# FastTrig_Board.net
KiCad netlist of a schematic drawn in Altium Designer
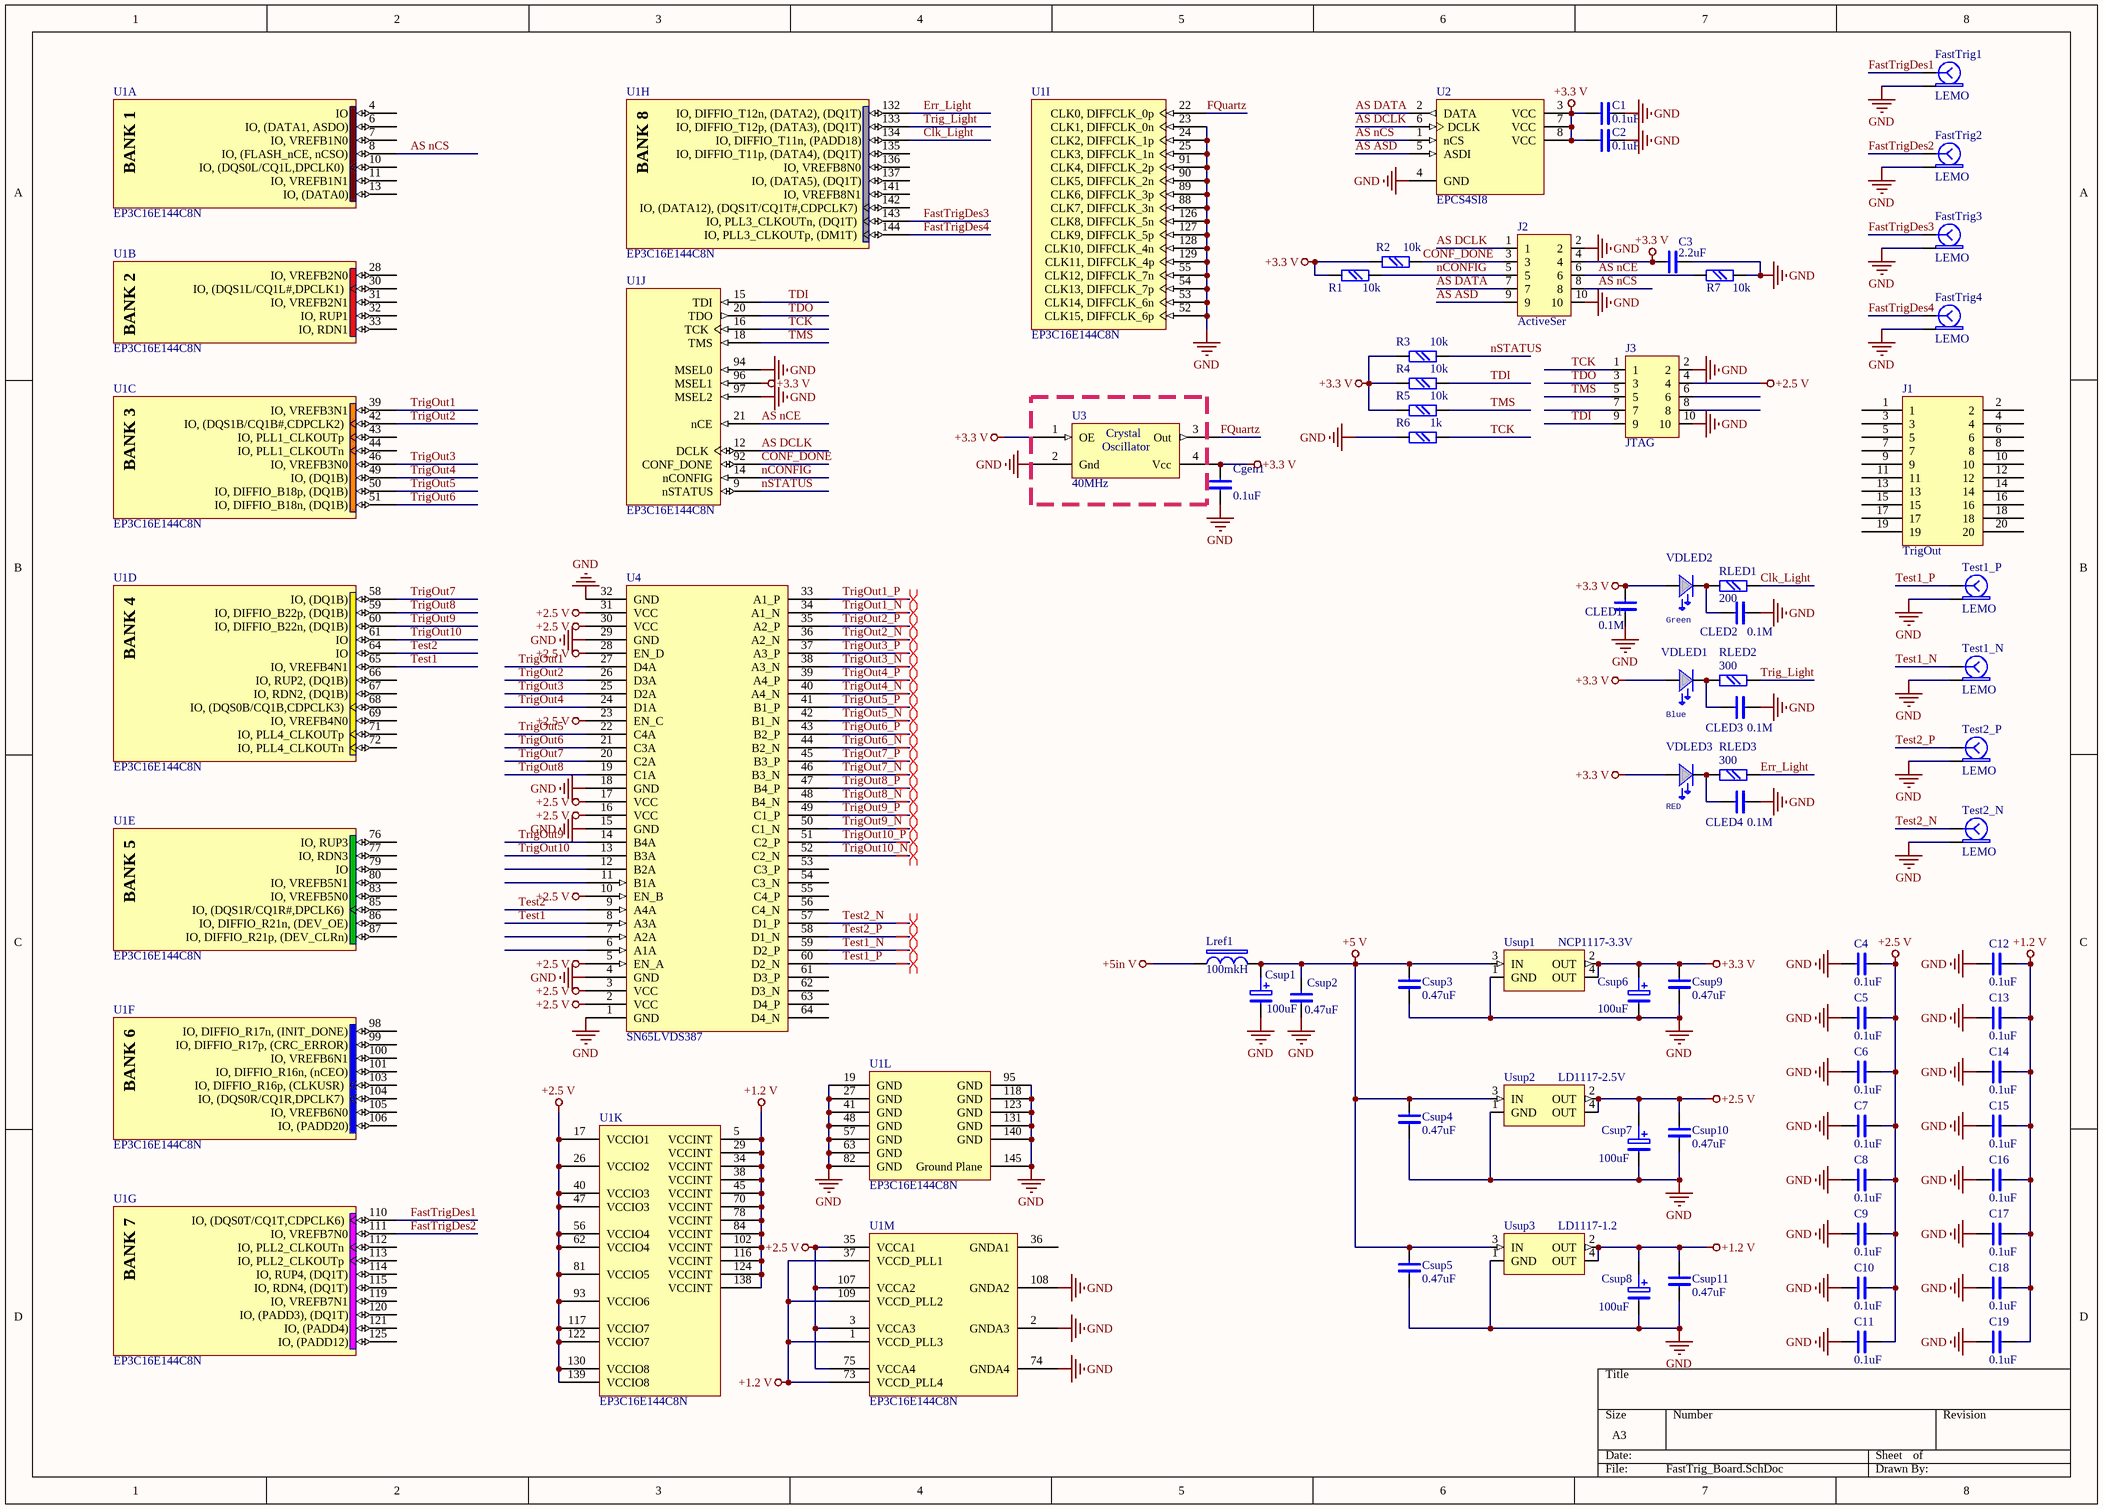
[diagram p0: FastTrig_Board.SchDoc]

(export (version "E")
  (design (tool "Eeschema 10.0.6"))
  (components
    (comp (ref "C1") (value "0.1uF") (footprint "chip0603") (libsource (lib "") (part "C_1")))
    (comp (ref "C2") (value "0.1uF") (footprint "chip0603") (libsource (lib "") (part "C_1")))
    (comp (ref "C3") (value "2.2uF") (footprint "chip0603") (libsource (lib "") (part "C_1")))
    (comp (ref "C4") (value "0.1uF") (footprint "chip0402") (libsource (lib "") (part "C_1")))
    (comp (ref "C5") (value "0.1uF") (footprint "chip0402") (libsource (lib "") (part "C_1")))
    (comp (ref "C6") (value "0.1uF") (footprint "chip0402") (libsource (lib "") (part "C_1")))
    (comp (ref "C7") (value "0.1uF") (footprint "chip0402") (libsource (lib "") (part "C_1")))
    (comp (ref "C8") (value "0.1uF") (footprint "chip0402") (libsource (lib "") (part "C_1")))
    (comp (ref "C9") (value "0.1uF") (footprint "chip0402") (libsource (lib "") (part "C_1")))
    (comp (ref "C10") (value "0.1uF") (footprint "chip0402") (libsource (lib "") (part "C_1")))
    (comp (ref "C11") (value "0.1uF") (footprint "chip0402") (libsource (lib "") (part "C_1")))
    (comp (ref "C12") (value "0.1uF") (footprint "chip0402") (libsource (lib "") (part "C_1")))
    (comp (ref "C13") (value "0.1uF") (footprint "chip0402") (libsource (lib "") (part "C_1")))
    (comp (ref "C14") (value "0.1uF") (footprint "chip0402") (libsource (lib "") (part "C_1")))
    (comp (ref "C15") (value "0.1uF") (footprint "chip0402") (libsource (lib "") (part "C_1")))
    (comp (ref "C16") (value "0.1uF") (footprint "chip0402") (libsource (lib "") (part "C_1")))
    (comp (ref "C17") (value "0.1uF") (footprint "chip0402") (libsource (lib "") (part "C_1")))
    (comp (ref "C18") (value "0.1uF") (footprint "chip0402") (libsource (lib "") (part "C_1")))
    (comp (ref "C19") (value "0.1uF") (footprint "chip0402") (libsource (lib "") (part "C_1")))
    (comp (ref "Cgen1") (value "0.1uF") (footprint "chip0603") (libsource (lib "*") (part "C")))
    (comp (ref "CLED1") (value "0.1M") (footprint "chip0805") (libsource (lib "") (part "C_1")))
    (comp (ref "CLED2") (value "0.1M") (footprint "chip0805") (libsource (lib "") (part "C_1")))
    (comp (ref "CLED3") (value "0.1M") (footprint "chip0805") (libsource (lib "") (part "C_1")))
    (comp (ref "CLED4") (value "0.1M") (footprint "chip0805") (libsource (lib "") (part "C_1")))
    (comp (ref "Csup1") (value "100uF") (footprint "CEL-SMD300") (libsource (lib "*") (part "C POL")))
    (comp (ref "Csup2") (value "0.47uF") (footprint "chip0603") (libsource (lib "*") (part "C")))
    (comp (ref "Csup3") (value "0.47uF") (footprint "chip0603") (libsource (lib "*") (part "C")))
    (comp (ref "Csup4") (value "0.47uF") (footprint "chip0603") (libsource (lib "*") (part "C")))
    (comp (ref "Csup5") (value "0.47uF") (footprint "chip0603") (libsource (lib "*") (part "C")))
    (comp (ref "Csup6") (value "100uF") (footprint "CEL-SMD300") (libsource (lib "*") (part "C POL")))
    (comp (ref "Csup7") (value "100uF") (footprint "CEL-SMD300") (libsource (lib "*") (part "C POL")))
    (comp (ref "Csup8") (value "100uF") (footprint "CEL-SMD300") (libsource (lib "*") (part "C POL")))
    (comp (ref "Csup9") (value "0.47uF") (footprint "chip0603") (libsource (lib "*") (part "C")))
    (comp (ref "Csup10") (value "0.47uF") (footprint "chip0603") (libsource (lib "*") (part "C")))
    (comp (ref "Csup11") (value "0.47uF") (footprint "chip0603") (libsource (lib "*") (part "C")))
    (comp (ref "FastTrig1") (value "LEMO") (footprint "LEMO") (libsource (lib "vDevice") (part "LEMO")))
    (comp (ref "FastTrig2") (value "LEMO") (footprint "LEMO") (libsource (lib "vDevice") (part "LEMO")))
    (comp (ref "FastTrig3") (value "LEMO") (footprint "LEMO") (libsource (lib "vDevice") (part "LEMO")))
    (comp (ref "FastTrig4") (value "LEMO") (footprint "LEMO") (libsource (lib "vDevice") (part "LEMO")))
    (comp (ref "J1")
      (value "TrigOut")
      (footprint "IDC-20_2x10_1.27")
      (libsource (lib "vDevice") (part "IDC-20_2x10_1.27"))
    )
    (comp (ref "J2") (value "ActiveSer") (footprint "IDC10") (libsource (lib "vDevice") (part "IDC-10")))
    (comp (ref "J3") (value "JTAG") (footprint "IDC10") (libsource (lib "vDevice") (part "IDC-10")))
    (comp (ref "Lref1") (value "100mkH") (footprint "SDR0604") (libsource (lib "*") (part "DR")))
    (comp (ref "R1") (value "10k") (footprint "chip0603") (libsource (lib "*") (part "R")))
    (comp (ref "R2") (value "10k") (footprint "chip0603") (libsource (lib "*") (part "R")))
    (comp (ref "R3") (value "10k") (footprint "chip0603") (libsource (lib "*") (part "R")))
    (comp (ref "R4") (value "10k") (footprint "chip0603") (libsource (lib "*") (part "R")))
    (comp (ref "R5") (value "10k") (footprint "chip0603") (libsource (lib "*") (part "R")))
    (comp (ref "R6") (value "1k") (footprint "chip0603") (libsource (lib "*") (part "R")))
    (comp (ref "R7") (value "10k") (footprint "chip0603") (libsource (lib "*") (part "R")))
    (comp (ref "RLED1") (value "200") (footprint "chip0805") (libsource (lib "*") (part "R")))
    (comp (ref "RLED2") (value "300") (footprint "chip0805") (libsource (lib "*") (part "R")))
    (comp (ref "RLED3") (value "300") (footprint "chip0805") (libsource (lib "*") (part "R")))
    (comp (ref "Test1_N") (value "LEMO") (footprint "LEMO") (libsource (lib "vDevice") (part "LEMO")))
    (comp (ref "Test1_P") (value "LEMO") (footprint "LEMO") (libsource (lib "vDevice") (part "LEMO")))
    (comp (ref "Test2_N") (value "LEMO") (footprint "LEMO") (libsource (lib "vDevice") (part "LEMO")))
    (comp (ref "Test2_P") (value "LEMO") (footprint "LEMO") (libsource (lib "vDevice") (part "LEMO")))
    (comp (ref "U1")
      (value "EP3C16E144C8N")
      (footprint "EQFP144_N")
      (fields (field (name "PUBLISHER") "Altium Limited"))
      (libsource (lib "") (part "EP3C16E144C8N_1"))
    )
    (comp (ref "U2")
      (value "EPCS4SI8")
      (footprint "8SO200")
      (fields (field (name "PUBLISHER") "Altium Limited"))
      (libsource (lib "Altera EPCS Configuration Device") (part "EPCS4SI8"))
    )
    (comp (ref "U3")
      (value "40MHz")
      (footprint "SG-636")
      (description "Crystal Oscillator (SMD)")
      (libsource (lib "*") (part "SG-636"))
    )
    (comp (ref "U4")
      (value "SN65LVDS387")
      (footprint "DGG064")
      (libsource (lib "vDigital") (part "SN65LVDS387"))
    )
    (comp (ref "Usup1")
      (value "NCP1117-3.3V")
      (footprint "TO-252")
      (libsource (lib "vAnalog") (part "NCP1117-3.3V"))
    )
    (comp (ref "Usup2")
      (value "LD1117-2.5V")
      (footprint "TO-252")
      (libsource (lib "vAnalog") (part "NCP1117-3.3V"))
    )
    (comp (ref "Usup3")
      (value "LD1117-1.2")
      (footprint "TO-252")
      (libsource (lib "vAnalog") (part "NCP1117-3.3V"))
    )
    (comp (ref "VDLED1") (value "LED") (footprint "CHIP1206") (libsource (lib "*") (part "AL307")))
    (comp (ref "VDLED2") (value "LED") (footprint "CHIP0805") (libsource (lib "*") (part "AL307")))
    (comp (ref "VDLED3") (value "LED") (footprint "CHIP1206") (libsource (lib "*") (part "AL307")))
  )
  (nets
    (net (code "1") (name "+1.2 V") (class "Default")
      (node (ref "C12") (pin "2") (pinfunction "2_2") (pintype "passive"))
      (node (ref "C13") (pin "2") (pinfunction "2_2") (pintype "passive"))
      (node (ref "C14") (pin "2") (pinfunction "2_2") (pintype "passive"))
      (node (ref "C15") (pin "2") (pinfunction "2_2") (pintype "passive"))
      (node (ref "C16") (pin "2") (pinfunction "2_2") (pintype "passive"))
      (node (ref "C17") (pin "2") (pinfunction "2_2") (pintype "passive"))
      (node (ref "C18") (pin "2") (pinfunction "2_2") (pintype "passive"))
      (node (ref "C19") (pin "2") (pinfunction "2_2") (pintype "passive"))
      (node (ref "Csup11") (pin "1") (pinfunction "1_1") (pintype "passive"))
      (node (ref "Csup8") (pin "+") (pinfunction "+_+") (pintype "passive"))
      (node (ref "U1") (pin "1") (pinfunction "VCCD_PLL3_1") (pintype "power_in"))
      (node (ref "U1") (pin "102") (pinfunction "VCCINT_102") (pintype "power_in"))
      (node (ref "U1") (pin "109") (pinfunction "VCCD_PLL2_109") (pintype "power_in"))
      (node (ref "U1") (pin "116") (pinfunction "VCCINT_116") (pintype "power_in"))
      (node (ref "U1") (pin "124") (pinfunction "VCCINT_124") (pintype "power_in"))
      (node (ref "U1") (pin "138") (pinfunction "VCCINT_138") (pintype "power_in"))
      (node (ref "U1") (pin "29") (pinfunction "VCCINT_29") (pintype "power_in"))
      (node (ref "U1") (pin "34") (pinfunction "VCCINT_34") (pintype "power_in"))
      (node (ref "U1") (pin "37") (pinfunction "VCCD_PLL1_37") (pintype "power_in"))
      (node (ref "U1") (pin "38") (pinfunction "VCCINT_38") (pintype "power_in"))
      (node (ref "U1") (pin "45") (pinfunction "VCCINT_45") (pintype "power_in"))
      (node (ref "U1") (pin "5") (pinfunction "VCCINT_5") (pintype "power_in"))
      (node (ref "U1") (pin "70") (pinfunction "VCCINT_70") (pintype "power_in"))
      (node (ref "U1") (pin "73") (pinfunction "VCCD_PLL4_73") (pintype "power_in"))
      (node (ref "U1") (pin "78") (pinfunction "VCCINT_78") (pintype "power_in"))
      (node (ref "U1") (pin "84") (pinfunction "VCCINT_84") (pintype "power_in"))
      (node (ref "Usup3") (pin "2") (pinfunction "OUT_2") (pintype "output"))
      (node (ref "Usup3") (pin "4") (pinfunction "OUT_4") (pintype "passive"))
    )
    (net (code "2") (name "+2.5 V") (class "Default")
      (node (ref "C10") (pin "2") (pinfunction "2_2") (pintype "passive"))
      (node (ref "C11") (pin "2") (pinfunction "2_2") (pintype "passive"))
      (node (ref "C4") (pin "2") (pinfunction "2_2") (pintype "passive"))
      (node (ref "C5") (pin "2") (pinfunction "2_2") (pintype "passive"))
      (node (ref "C6") (pin "2") (pinfunction "2_2") (pintype "passive"))
      (node (ref "C7") (pin "2") (pinfunction "2_2") (pintype "passive"))
      (node (ref "C8") (pin "2") (pinfunction "2_2") (pintype "passive"))
      (node (ref "C9") (pin "2") (pinfunction "2_2") (pintype "passive"))
      (node (ref "Csup10") (pin "1") (pinfunction "1_1") (pintype "passive"))
      (node (ref "Csup7") (pin "+") (pinfunction "+_+") (pintype "passive"))
      (node (ref "J3") (pin "4") (pinfunction "4_4") (pintype "bidirectional"))
      (node (ref "U1") (pin "107") (pinfunction "VCCA2_107") (pintype "power_in"))
      (node (ref "U1") (pin "117") (pinfunction "VCCIO7_117") (pintype "power_in"))
      (node (ref "U1") (pin "122") (pinfunction "VCCIO7_122") (pintype "power_in"))
      (node (ref "U1") (pin "130") (pinfunction "VCCIO8_130") (pintype "power_in"))
      (node (ref "U1") (pin "139") (pinfunction "VCCIO8_139") (pintype "power_in"))
      (node (ref "U1") (pin "17") (pinfunction "VCCIO1_17") (pintype "power_in"))
      (node (ref "U1") (pin "26") (pinfunction "VCCIO2_26") (pintype "power_in"))
      (node (ref "U1") (pin "3") (pinfunction "VCCA3_3") (pintype "power_in"))
      (node (ref "U1") (pin "35") (pinfunction "VCCA1_35") (pintype "power_in"))
      (node (ref "U1") (pin "40") (pinfunction "VCCIO3_40") (pintype "power_in"))
      (node (ref "U1") (pin "47") (pinfunction "VCCIO3_47") (pintype "power_in"))
      (node (ref "U1") (pin "56") (pinfunction "VCCIO4_56") (pintype "power_in"))
      (node (ref "U1") (pin "62") (pinfunction "VCCIO4_62") (pintype "power_in"))
      (node (ref "U1") (pin "75") (pinfunction "VCCA4_75") (pintype "power_in"))
      (node (ref "U1") (pin "81") (pinfunction "VCCIO5_81") (pintype "power_in"))
      (node (ref "U1") (pin "93") (pinfunction "VCCIO6_93") (pintype "power_in"))
      (node (ref "U4") (pin "10") (pinfunction "EN_B_10") (pintype "input"))
      (node (ref "U4") (pin "16") (pinfunction "VCC_16") (pintype "power_in"))
      (node (ref "U4") (pin "17") (pinfunction "VCC_17") (pintype "power_in"))
      (node (ref "U4") (pin "2") (pinfunction "VCC_2") (pintype "power_in"))
      (node (ref "U4") (pin "23") (pinfunction "EN_C_23") (pintype "passive"))
      (node (ref "U4") (pin "28") (pinfunction "EN_D_28") (pintype "passive"))
      (node (ref "U4") (pin "3") (pinfunction "VCC_3") (pintype "power_in"))
      (node (ref "U4") (pin "30") (pinfunction "VCC_30") (pintype "power_in"))
      (node (ref "U4") (pin "31") (pinfunction "VCC_31") (pintype "power_in"))
      (node (ref "U4") (pin "5") (pinfunction "EN_A_5") (pintype "input"))
      (node (ref "Usup2") (pin "2") (pinfunction "OUT_2") (pintype "output"))
      (node (ref "Usup2") (pin "4") (pinfunction "OUT_4") (pintype "passive"))
    )
    (net (code "3") (name "+3.3 V") (class "Default")
      (node (ref "C1") (pin "2") (pinfunction "2_2") (pintype "passive"))
      (node (ref "C2") (pin "2") (pinfunction "2_2") (pintype "passive"))
      (node (ref "C3") (pin "1") (pinfunction "1_1") (pintype "passive"))
      (node (ref "CLED1") (pin "1") (pinfunction "1_1") (pintype "passive"))
      (node (ref "Cgen1") (pin "2") (pinfunction "2_2") (pintype "passive"))
      (node (ref "Csup6") (pin "+") (pinfunction "+_+") (pintype "passive"))
      (node (ref "Csup9") (pin "1") (pinfunction "1_1") (pintype "passive"))
      (node (ref "J2") (pin "4") (pinfunction "4_4") (pintype "bidirectional"))
      (node (ref "R1") (pin "1") (pinfunction "1_1") (pintype "passive"))
      (node (ref "R2") (pin "1") (pinfunction "1_1") (pintype "passive"))
      (node (ref "R3") (pin "1") (pinfunction "1_1") (pintype "passive"))
      (node (ref "R4") (pin "1") (pinfunction "1_1") (pintype "passive"))
      (node (ref "R5") (pin "1") (pinfunction "1_1") (pintype "passive"))
      (node (ref "U1") (pin "96") (pinfunction "MSEL1_96") (pintype "input"))
      (node (ref "U2") (pin "3") (pinfunction "VCC_3") (pintype "power_in"))
      (node (ref "U2") (pin "7") (pinfunction "VCC_7") (pintype "power_in"))
      (node (ref "U2") (pin "8") (pinfunction "VCC_8") (pintype "power_in"))
      (node (ref "U3") (pin "1") (pinfunction "OE_1") (pintype "input"))
      (node (ref "U3") (pin "4") (pinfunction "Vcc_4") (pintype "power_in"))
      (node (ref "Usup1") (pin "2") (pinfunction "OUT_2") (pintype "output"))
      (node (ref "Usup1") (pin "4") (pinfunction "OUT_4") (pintype "passive"))
      (node (ref "VDLED1") (pin "ANOD") (pinfunction "ANOD_ANOD") (pintype "passive"))
      (node (ref "VDLED2") (pin "ANOD") (pinfunction "ANOD_ANOD") (pintype "passive"))
      (node (ref "VDLED3") (pin "ANOD") (pinfunction "ANOD_ANOD") (pintype "passive"))
    )
    (net (code "4") (name "+5 V") (class "Default")
      (node (ref "Csup1") (pin "+") (pinfunction "+_+") (pintype "passive"))
      (node (ref "Csup2") (pin "1") (pinfunction "1_1") (pintype "passive"))
      (node (ref "Csup3") (pin "1") (pinfunction "1_1") (pintype "passive"))
      (node (ref "Csup4") (pin "1") (pinfunction "1_1") (pintype "passive"))
      (node (ref "Csup5") (pin "1") (pinfunction "1_1") (pintype "passive"))
      (node (ref "Lref1") (pin "2") (pinfunction "2_2") (pintype "passive"))
      (node (ref "Usup1") (pin "3") (pinfunction "IN_3") (pintype "input"))
      (node (ref "Usup2") (pin "3") (pinfunction "IN_3") (pintype "input"))
      (node (ref "Usup3") (pin "3") (pinfunction "IN_3") (pintype "input"))
    )
    (net (code "5") (name "+5in V") (class "Default")
      (node (ref "Lref1") (pin "1") (pinfunction "1_1") (pintype "passive"))
    )
    (net (code "6") (name "/AS ASD") (class "Default")
      (node (ref "J2") (pin "9") (pinfunction "9_9") (pintype "bidirectional"))
      (node (ref "U2") (pin "5") (pinfunction "ASDI_5") (pintype "input"))
    )
    (net (code "7") (name "/AS DATA") (class "Default")
      (node (ref "J2") (pin "7") (pinfunction "7_7") (pintype "bidirectional"))
      (node (ref "U2") (pin "2") (pinfunction "DATA_2") (pintype "output"))
    )
    (net (code "8") (name "/AS DCLK") (class "Default")
      (node (ref "J2") (pin "1") (pinfunction "1_1") (pintype "bidirectional"))
      (node (ref "U1") (pin "12") (pinfunction "DCLK_12") (pintype "bidirectional"))
      (node (ref "U2") (pin "6") (pinfunction "DCLK_6") (pintype "input"))
    )
    (net (code "9") (name "/AS nCE") (class "Default")
      (node (ref "J2") (pin "6") (pinfunction "6_6") (pintype "bidirectional"))
      (node (ref "R7") (pin "1") (pinfunction "1_1") (pintype "passive"))
      (node (ref "U1") (pin "21") (pinfunction "nCE_21") (pintype "input"))
    )
    (net (code "10") (name "/AS nCS") (class "Default")
      (node (ref "J2") (pin "8") (pinfunction "8_8") (pintype "bidirectional"))
      (node (ref "U1") (pin "8") (pinfunction "IO,_(FLASH_nCE,_nCSO)_8") (pintype "bidirectional"))
      (node (ref "U2") (pin "1") (pinfunction "nCS_1") (pintype "input"))
    )
    (net (code "11") (name "/CONF_DONE") (class "Default")
      (node (ref "J2") (pin "3") (pinfunction "3_3") (pintype "bidirectional"))
      (node (ref "R2") (pin "2") (pinfunction "2_2") (pintype "passive"))
      (node (ref "U1") (pin "92") (pinfunction "CONF_DONE_92") (pintype "bidirectional"))
    )
    (net (code "12") (name "/Clk_Light") (class "Default")
      (node (ref "RLED1") (pin "2") (pinfunction "2_2") (pintype "passive"))
      (node (ref "U1") (pin "134") (pinfunction "IO,_DIFFIO_T11n,_(PADD18)_134") (pintype "bidirectional"))
    )
    (net (code "13") (name "/Err_Light") (class "Default")
      (node (ref "RLED3") (pin "2") (pinfunction "2_2") (pintype "passive"))
      (node (ref "U1") (pin "132") (pinfunction "IO,_DIFFIO_T12n,_(DATA2),_(DQ1T)_132") (pintype "bidirectional"))
    )
    (net (code "14") (name "/FQuartz") (class "Default")
      (node (ref "U1") (pin "22") (pinfunction "CLK0,_DIFFCLK_0p_22") (pintype "input"))
      (node (ref "U3") (pin "3") (pinfunction "Out_3") (pintype "output"))
    )
    (net (code "15") (name "/FastTrigDes1") (class "Default")
      (node (ref "FastTrig1") (pin "WIRE") (pinfunction "WIRE_WIRE") (pintype "bidirectional"))
      (node (ref "U1") (pin "110") (pinfunction "IO,_(DQS0T/CQ1T,CDPCLK6)_110") (pintype "bidirectional"))
    )
    (net (code "16") (name "/FastTrigDes2") (class "Default")
      (node (ref "FastTrig2") (pin "WIRE") (pinfunction "WIRE_WIRE") (pintype "bidirectional"))
      (node (ref "U1") (pin "111") (pinfunction "IO,_VREFB7N0_111") (pintype "bidirectional"))
    )
    (net (code "17") (name "/FastTrigDes3") (class "Default")
      (node (ref "FastTrig3") (pin "WIRE") (pinfunction "WIRE_WIRE") (pintype "bidirectional"))
      (node (ref "U1") (pin "143") (pinfunction "IO,_PLL3_CLKOUTn,_(DQ1T)_143") (pintype "bidirectional"))
    )
    (net (code "18") (name "/FastTrigDes4") (class "Default")
      (node (ref "FastTrig4") (pin "WIRE") (pinfunction "WIRE_WIRE") (pintype "bidirectional"))
      (node (ref "U1") (pin "144") (pinfunction "IO,_PLL3_CLKOUTp,_(DM1T)_144") (pintype "bidirectional"))
    )
    (net (code "19") (name "/TCK") (class "Default")
      (node (ref "J3") (pin "1") (pinfunction "1_1") (pintype "bidirectional"))
      (node (ref "R6") (pin "2") (pinfunction "2_2") (pintype "passive"))
      (node (ref "U1") (pin "16") (pinfunction "TCK_16") (pintype "input"))
    )
    (net (code "20") (name "/TDI") (class "Default")
      (node (ref "J3") (pin "9") (pinfunction "9_9") (pintype "bidirectional"))
      (node (ref "R4") (pin "2") (pinfunction "2_2") (pintype "passive"))
      (node (ref "U1") (pin "15") (pinfunction "TDI_15") (pintype "input"))
    )
    (net (code "21") (name "/TDO") (class "Default")
      (node (ref "J3") (pin "3") (pinfunction "3_3") (pintype "bidirectional"))
      (node (ref "U1") (pin "20") (pinfunction "TDO_20") (pintype "output"))
    )
    (net (code "22") (name "/TMS") (class "Default")
      (node (ref "J3") (pin "5") (pinfunction "5_5") (pintype "bidirectional"))
      (node (ref "R5") (pin "2") (pinfunction "2_2") (pintype "passive"))
      (node (ref "U1") (pin "18") (pinfunction "TMS_18") (pintype "input"))
    )
    (net (code "23") (name "/Test1") (class "Default")
      (node (ref "U1") (pin "65") (pinfunction "IO,_VREFB4N1_65") (pintype "bidirectional"))
      (node (ref "U4") (pin "8") (pinfunction "A3A_8") (pintype "input"))
    )
    (net (code "24") (name "/Test1_N") (class "Default")
      (node (ref "Test1_N") (pin "WIRE") (pinfunction "WIRE_WIRE") (pintype "bidirectional"))
      (node (ref "U4") (pin "59") (pinfunction "D2_P_59") (pintype "passive"))
    )
    (net (code "25") (name "/Test1_P") (class "Default")
      (node (ref "Test1_P") (pin "WIRE") (pinfunction "WIRE_WIRE") (pintype "bidirectional"))
      (node (ref "U4") (pin "60") (pinfunction "D2_N_60") (pintype "passive"))
    )
    (net (code "26") (name "/Test2") (class "Default")
      (node (ref "U1") (pin "64") (pinfunction "IO_64") (pintype "bidirectional"))
      (node (ref "U4") (pin "9") (pinfunction "A4A_9") (pintype "input"))
    )
    (net (code "27") (name "/Test2_N") (class "Default")
      (node (ref "Test2_N") (pin "WIRE") (pinfunction "WIRE_WIRE") (pintype "bidirectional"))
      (node (ref "U4") (pin "57") (pinfunction "D1_P_57") (pintype "passive"))
    )
    (net (code "28") (name "/Test2_P") (class "Default")
      (node (ref "Test2_P") (pin "WIRE") (pinfunction "WIRE_WIRE") (pintype "bidirectional"))
      (node (ref "U4") (pin "58") (pinfunction "D1_N_58") (pintype "passive"))
    )
    (net (code "29") (name "/TrigOut1") (class "Default")
      (node (ref "U1") (pin "39") (pinfunction "IO,_VREFB3N1_39") (pintype "bidirectional"))
      (node (ref "U4") (pin "27") (pinfunction "D4A_27") (pintype "passive"))
    )
    (net (code "30") (name "/TrigOut1_N") (class "Default")
      (node (ref "U4") (pin "34") (pinfunction "A1_N_34") (pintype "passive"))
    )
    (net (code "31") (name "/TrigOut1_P") (class "Default")
      (node (ref "U4") (pin "33") (pinfunction "A1_P_33") (pintype "passive"))
    )
    (net (code "32") (name "/TrigOut2") (class "Default")
      (node (ref "U1") (pin "42") (pinfunction "IO,_(DQS1B/CQ1B#,CDPCLK2)_42") (pintype "bidirectional"))
      (node (ref "U4") (pin "26") (pinfunction "D3A_26") (pintype "passive"))
    )
    (net (code "33") (name "/TrigOut2_N") (class "Default")
      (node (ref "U4") (pin "36") (pinfunction "A2_N_36") (pintype "passive"))
    )
    (net (code "34") (name "/TrigOut2_P") (class "Default")
      (node (ref "U4") (pin "35") (pinfunction "A2_P_35") (pintype "passive"))
    )
    (net (code "35") (name "/TrigOut3") (class "Default")
      (node (ref "U1") (pin "46") (pinfunction "IO,_VREFB3N0_46") (pintype "bidirectional"))
      (node (ref "U4") (pin "25") (pinfunction "D2A_25") (pintype "passive"))
    )
    (net (code "36") (name "/TrigOut3_N") (class "Default")
      (node (ref "U4") (pin "38") (pinfunction "A3_N_38") (pintype "passive"))
    )
    (net (code "37") (name "/TrigOut3_P") (class "Default")
      (node (ref "U4") (pin "37") (pinfunction "A3_P_37") (pintype "passive"))
    )
    (net (code "38") (name "/TrigOut4") (class "Default")
      (node (ref "U1") (pin "49") (pinfunction "IO,_(DQ1B)_49") (pintype "bidirectional"))
      (node (ref "U4") (pin "24") (pinfunction "D1A_24") (pintype "passive"))
    )
    (net (code "39") (name "/TrigOut4_N") (class "Default")
      (node (ref "U4") (pin "40") (pinfunction "A4_N_40") (pintype "passive"))
    )
    (net (code "40") (name "/TrigOut4_P") (class "Default")
      (node (ref "U4") (pin "39") (pinfunction "A4_P_39") (pintype "passive"))
    )
    (net (code "41") (name "/TrigOut5") (class "Default")
      (node (ref "U1") (pin "50") (pinfunction "IO,_DIFFIO_B18p,_(DQ1B)_50") (pintype "bidirectional"))
      (node (ref "U4") (pin "22") (pinfunction "C4A_22") (pintype "passive"))
    )
    (net (code "42") (name "/TrigOut5_N") (class "Default")
      (node (ref "U4") (pin "42") (pinfunction "B1_N_42") (pintype "passive"))
    )
    (net (code "43") (name "/TrigOut5_P") (class "Default")
      (node (ref "U4") (pin "41") (pinfunction "B1_P_41") (pintype "passive"))
    )
    (net (code "44") (name "/TrigOut6") (class "Default")
      (node (ref "U1") (pin "51") (pinfunction "IO,_DIFFIO_B18n,_(DQ1B)_51") (pintype "bidirectional"))
      (node (ref "U4") (pin "21") (pinfunction "C3A_21") (pintype "passive"))
    )
    (net (code "45") (name "/TrigOut6_N") (class "Default")
      (node (ref "U4") (pin "44") (pinfunction "B2_N_44") (pintype "passive"))
    )
    (net (code "46") (name "/TrigOut6_P") (class "Default")
      (node (ref "U4") (pin "43") (pinfunction "B2_P_43") (pintype "passive"))
    )
    (net (code "47") (name "/TrigOut7") (class "Default")
      (node (ref "U1") (pin "58") (pinfunction "IO,_(DQ1B)_58") (pintype "bidirectional"))
      (node (ref "U4") (pin "20") (pinfunction "C2A_20") (pintype "passive"))
    )
    (net (code "48") (name "/TrigOut7_N") (class "Default")
      (node (ref "U4") (pin "46") (pinfunction "B3_N_46") (pintype "passive"))
    )
    (net (code "49") (name "/TrigOut7_P") (class "Default")
      (node (ref "U4") (pin "45") (pinfunction "B3_P_45") (pintype "passive"))
    )
    (net (code "50") (name "/TrigOut8") (class "Default")
      (node (ref "U1") (pin "59") (pinfunction "IO,_DIFFIO_B22p,_(DQ1B)_59") (pintype "bidirectional"))
      (node (ref "U4") (pin "19") (pinfunction "C1A_19") (pintype "passive"))
    )
    (net (code "51") (name "/TrigOut8_N") (class "Default")
      (node (ref "U4") (pin "48") (pinfunction "B4_N_48") (pintype "passive"))
    )
    (net (code "52") (name "/TrigOut8_P") (class "Default")
      (node (ref "U4") (pin "47") (pinfunction "B4_P_47") (pintype "passive"))
    )
    (net (code "53") (name "/TrigOut9") (class "Default")
      (node (ref "U1") (pin "60") (pinfunction "IO,_DIFFIO_B22n,_(DQ1B)_60") (pintype "bidirectional"))
      (node (ref "U4") (pin "14") (pinfunction "B4A_14") (pintype "passive"))
    )
    (net (code "54") (name "/TrigOut9_N") (class "Default")
      (node (ref "U4") (pin "50") (pinfunction "C1_N_50") (pintype "passive"))
    )
    (net (code "55") (name "/TrigOut9_P") (class "Default")
      (node (ref "U4") (pin "49") (pinfunction "C1_P_49") (pintype "passive"))
    )
    (net (code "56") (name "/TrigOut10") (class "Default")
      (node (ref "U1") (pin "61") (pinfunction "IO_61") (pintype "bidirectional"))
      (node (ref "U4") (pin "13") (pinfunction "B3A_13") (pintype "passive"))
    )
    (net (code "57") (name "/TrigOut10_N") (class "Default")
      (node (ref "U4") (pin "52") (pinfunction "C2_N_52") (pintype "passive"))
    )
    (net (code "58") (name "/TrigOut10_P") (class "Default")
      (node (ref "U4") (pin "51") (pinfunction "C2_P_51") (pintype "passive"))
    )
    (net (code "59") (name "/Trig_Light") (class "Default")
      (node (ref "RLED2") (pin "2") (pinfunction "2_2") (pintype "passive"))
      (node (ref "U1") (pin "133") (pinfunction "IO,_DIFFIO_T12p,_(DATA3),_(DQ1T)_133") (pintype "bidirectional"))
    )
    (net (code "60") (name "/nCONFIG") (class "Default")
      (node (ref "J2") (pin "5") (pinfunction "5_5") (pintype "bidirectional"))
      (node (ref "R1") (pin "2") (pinfunction "2_2") (pintype "passive"))
      (node (ref "U1") (pin "14") (pinfunction "nCONFIG_14") (pintype "input"))
    )
    (net (code "61") (name "/nSTATUS") (class "Default")
      (node (ref "R3") (pin "2") (pinfunction "2_2") (pintype "passive"))
      (node (ref "U1") (pin "9") (pinfunction "nSTATUS_9") (pintype "bidirectional"))
    )
    (net (code "62") (name "GND") (class "Default")
      (node (ref "C1") (pin "1") (pinfunction "1_1") (pintype "passive"))
      (node (ref "C10") (pin "1") (pinfunction "1_1") (pintype "passive"))
      (node (ref "C11") (pin "1") (pinfunction "1_1") (pintype "passive"))
      (node (ref "C12") (pin "1") (pinfunction "1_1") (pintype "passive"))
      (node (ref "C13") (pin "1") (pinfunction "1_1") (pintype "passive"))
      (node (ref "C14") (pin "1") (pinfunction "1_1") (pintype "passive"))
      (node (ref "C15") (pin "1") (pinfunction "1_1") (pintype "passive"))
      (node (ref "C16") (pin "1") (pinfunction "1_1") (pintype "passive"))
      (node (ref "C17") (pin "1") (pinfunction "1_1") (pintype "passive"))
      (node (ref "C18") (pin "1") (pinfunction "1_1") (pintype "passive"))
      (node (ref "C19") (pin "1") (pinfunction "1_1") (pintype "passive"))
      (node (ref "C2") (pin "1") (pinfunction "1_1") (pintype "passive"))
      (node (ref "C3") (pin "2") (pinfunction "2_2") (pintype "passive"))
      (node (ref "C4") (pin "1") (pinfunction "1_1") (pintype "passive"))
      (node (ref "C5") (pin "1") (pinfunction "1_1") (pintype "passive"))
      (node (ref "C6") (pin "1") (pinfunction "1_1") (pintype "passive"))
      (node (ref "C7") (pin "1") (pinfunction "1_1") (pintype "passive"))
      (node (ref "C8") (pin "1") (pinfunction "1_1") (pintype "passive"))
      (node (ref "C9") (pin "1") (pinfunction "1_1") (pintype "passive"))
      (node (ref "CLED1") (pin "2") (pinfunction "2_2") (pintype "passive"))
      (node (ref "CLED2") (pin "2") (pinfunction "2_2") (pintype "passive"))
      (node (ref "CLED3") (pin "2") (pinfunction "2_2") (pintype "passive"))
      (node (ref "CLED4") (pin "2") (pinfunction "2_2") (pintype "passive"))
      (node (ref "Cgen1") (pin "1") (pinfunction "1_1") (pintype "passive"))
      (node (ref "Csup1") (pin "-") (pinfunction "-_-") (pintype "passive"))
      (node (ref "Csup10") (pin "2") (pinfunction "2_2") (pintype "passive"))
      (node (ref "Csup11") (pin "2") (pinfunction "2_2") (pintype "passive"))
      (node (ref "Csup2") (pin "2") (pinfunction "2_2") (pintype "passive"))
      (node (ref "Csup3") (pin "2") (pinfunction "2_2") (pintype "passive"))
      (node (ref "Csup4") (pin "2") (pinfunction "2_2") (pintype "passive"))
      (node (ref "Csup5") (pin "2") (pinfunction "2_2") (pintype "passive"))
      (node (ref "Csup6") (pin "-") (pinfunction "-_-") (pintype "passive"))
      (node (ref "Csup7") (pin "-") (pinfunction "-_-") (pintype "passive"))
      (node (ref "Csup8") (pin "-") (pinfunction "-_-") (pintype "passive"))
      (node (ref "Csup9") (pin "2") (pinfunction "2_2") (pintype "passive"))
      (node (ref "FastTrig1") (pin "SHIELD") (pinfunction "SHIELD_SHIELD") (pintype "bidirectional"))
      (node (ref "FastTrig2") (pin "SHIELD") (pinfunction "SHIELD_SHIELD") (pintype "bidirectional"))
      (node (ref "FastTrig3") (pin "SHIELD") (pinfunction "SHIELD_SHIELD") (pintype "bidirectional"))
      (node (ref "FastTrig4") (pin "SHIELD") (pinfunction "SHIELD_SHIELD") (pintype "bidirectional"))
      (node (ref "J2") (pin "10") (pinfunction "10_10") (pintype "bidirectional"))
      (node (ref "J2") (pin "2") (pinfunction "2_2") (pintype "bidirectional"))
      (node (ref "J3") (pin "10") (pinfunction "10_10") (pintype "bidirectional"))
      (node (ref "J3") (pin "2") (pinfunction "2_2") (pintype "bidirectional"))
      (node (ref "R6") (pin "1") (pinfunction "1_1") (pintype "passive"))
      (node (ref "R7") (pin "2") (pinfunction "2_2") (pintype "passive"))
      (node (ref "Test1_N") (pin "SHIELD") (pinfunction "SHIELD_SHIELD") (pintype "bidirectional"))
      (node (ref "Test1_P") (pin "SHIELD") (pinfunction "SHIELD_SHIELD") (pintype "bidirectional"))
      (node (ref "Test2_N") (pin "SHIELD") (pinfunction "SHIELD_SHIELD") (pintype "bidirectional"))
      (node (ref "Test2_P") (pin "SHIELD") (pinfunction "SHIELD_SHIELD") (pintype "bidirectional"))
      (node (ref "U1") (pin "108") (pinfunction "GNDA2_108") (pintype "power_in"))
      (node (ref "U1") (pin "118") (pinfunction "GND_118") (pintype "power_in"))
      (node (ref "U1") (pin "123") (pinfunction "GND_123") (pintype "power_in"))
      (node (ref "U1") (pin "126") (pinfunction "CLK8,_DIFFCLK_5n_126") (pintype "input"))
      (node (ref "U1") (pin "127") (pinfunction "CLK9,_DIFFCLK_5p_127") (pintype "input"))
      (node (ref "U1") (pin "128") (pinfunction "CLK10,_DIFFCLK_4n_128") (pintype "input"))
      (node (ref "U1") (pin "129") (pinfunction "CLK11,_DIFFCLK_4p_129") (pintype "input"))
      (node (ref "U1") (pin "131") (pinfunction "GND_131") (pintype "power_in"))
      (node (ref "U1") (pin "140") (pinfunction "GND_140") (pintype "power_in"))
      (node (ref "U1") (pin "145") (pinfunction "Ground_Plane_145") (pintype "power_in"))
      (node (ref "U1") (pin "19") (pinfunction "GND_19") (pintype "power_in"))
      (node (ref "U1") (pin "2") (pinfunction "GNDA3_2") (pintype "power_in"))
      (node (ref "U1") (pin "23") (pinfunction "CLK1,_DIFFCLK_0n_23") (pintype "input"))
      (node (ref "U1") (pin "24") (pinfunction "CLK2,_DIFFCLK_1p_24") (pintype "input"))
      (node (ref "U1") (pin "25") (pinfunction "CLK3,_DIFFCLK_1n_25") (pintype "input"))
      (node (ref "U1") (pin "27") (pinfunction "GND_27") (pintype "power_in"))
      (node (ref "U1") (pin "41") (pinfunction "GND_41") (pintype "power_in"))
      (node (ref "U1") (pin "48") (pinfunction "GND_48") (pintype "power_in"))
      (node (ref "U1") (pin "52") (pinfunction "CLK15,_DIFFCLK_6p_52") (pintype "input"))
      (node (ref "U1") (pin "53") (pinfunction "CLK14,_DIFFCLK_6n_53") (pintype "input"))
      (node (ref "U1") (pin "54") (pinfunction "CLK13,_DIFFCLK_7p_54") (pintype "input"))
      (node (ref "U1") (pin "55") (pinfunction "CLK12,_DIFFCLK_7n_55") (pintype "input"))
      (node (ref "U1") (pin "57") (pinfunction "GND_57") (pintype "power_in"))
      (node (ref "U1") (pin "63") (pinfunction "GND_63") (pintype "power_in"))
      (node (ref "U1") (pin "74") (pinfunction "GNDA4_74") (pintype "power_in"))
      (node (ref "U1") (pin "82") (pinfunction "GND_82") (pintype "power_in"))
      (node (ref "U1") (pin "88") (pinfunction "CLK7,_DIFFCLK_3n_88") (pintype "input"))
      (node (ref "U1") (pin "89") (pinfunction "CLK6,_DIFFCLK_3p_89") (pintype "input"))
      (node (ref "U1") (pin "90") (pinfunction "CLK5,_DIFFCLK_2n_90") (pintype "input"))
      (node (ref "U1") (pin "91") (pinfunction "CLK4,_DIFFCLK_2p_91") (pintype "input"))
      (node (ref "U1") (pin "94") (pinfunction "MSEL0_94") (pintype "input"))
      (node (ref "U1") (pin "95") (pinfunction "GND_95") (pintype "power_in"))
      (node (ref "U1") (pin "97") (pinfunction "MSEL2_97") (pintype "input"))
      (node (ref "U2") (pin "4") (pinfunction "GND_4") (pintype "power_in"))
      (node (ref "U3") (pin "2") (pinfunction "Gnd_2") (pintype "power_in"))
      (node (ref "U4") (pin "1") (pinfunction "GND_1") (pintype "power_in"))
      (node (ref "U4") (pin "15") (pinfunction "GND_15") (pintype "power_in"))
      (node (ref "U4") (pin "18") (pinfunction "GND_18") (pintype "power_in"))
      (node (ref "U4") (pin "29") (pinfunction "GND_29") (pintype "power_in"))
      (node (ref "U4") (pin "32") (pinfunction "GND_32") (pintype "power_in"))
      (node (ref "U4") (pin "4") (pinfunction "GND_4") (pintype "power_in"))
      (node (ref "Usup1") (pin "1") (pinfunction "GND_1") (pintype "power_in"))
      (node (ref "Usup2") (pin "1") (pinfunction "GND_1") (pintype "power_in"))
      (node (ref "Usup3") (pin "1") (pinfunction "GND_1") (pintype "power_in"))
    )
    (net (code "63") (name "Net-(CLED2-Pad1)") (class "Default")
      (node (ref "CLED2") (pin "1") (pinfunction "1_1") (pintype "passive"))
      (node (ref "RLED1") (pin "1") (pinfunction "1_1") (pintype "passive"))
      (node (ref "VDLED2") (pin "CATH") (pinfunction "CATH_CATH") (pintype "passive"))
    )
    (net (code "64") (name "Net-(CLED3-Pad1)") (class "Default")
      (node (ref "CLED3") (pin "1") (pinfunction "1_1") (pintype "passive"))
      (node (ref "RLED2") (pin "1") (pinfunction "1_1") (pintype "passive"))
      (node (ref "VDLED1") (pin "CATH") (pinfunction "CATH_CATH") (pintype "passive"))
    )
    (net (code "65") (name "Net-(CLED4-Pad1)") (class "Default")
      (node (ref "CLED4") (pin "1") (pinfunction "1_1") (pintype "passive"))
      (node (ref "RLED3") (pin "1") (pinfunction "1_1") (pintype "passive"))
      (node (ref "VDLED3") (pin "CATH") (pinfunction "CATH_CATH") (pintype "passive"))
    )
    (net (code "66") (name "unconnected-(J1-Pad1)") (class "Default")
      (node (ref "J1") (pin "1") (pinfunction "1_1") (pintype "passive"))
    )
    (net (code "67") (name "unconnected-(J1-Pad2)") (class "Default")
      (node (ref "J1") (pin "2") (pinfunction "2_2") (pintype "passive"))
    )
    (net (code "68") (name "unconnected-(J1-Pad3)") (class "Default")
      (node (ref "J1") (pin "3") (pinfunction "3_3") (pintype "passive"))
    )
    (net (code "69") (name "unconnected-(J1-Pad4)") (class "Default")
      (node (ref "J1") (pin "4") (pinfunction "4_4") (pintype "passive"))
    )
    (net (code "70") (name "unconnected-(J1-Pad5)") (class "Default")
      (node (ref "J1") (pin "5") (pinfunction "5_5") (pintype "passive"))
    )
    (net (code "71") (name "unconnected-(J1-Pad6)") (class "Default")
      (node (ref "J1") (pin "6") (pinfunction "6_6") (pintype "passive"))
    )
    (net (code "72") (name "unconnected-(J1-Pad7)") (class "Default")
      (node (ref "J1") (pin "7") (pinfunction "7_7") (pintype "passive"))
    )
    (net (code "73") (name "unconnected-(J1-Pad8)") (class "Default")
      (node (ref "J1") (pin "8") (pinfunction "8_8") (pintype "passive"))
    )
    (net (code "74") (name "unconnected-(J1-Pad9)") (class "Default")
      (node (ref "J1") (pin "9") (pinfunction "9_9") (pintype "passive"))
    )
    (net (code "75") (name "unconnected-(J1-Pad10)") (class "Default")
      (node (ref "J1") (pin "10") (pinfunction "10_10") (pintype "passive"))
    )
    (net (code "76") (name "unconnected-(J1-Pad11)") (class "Default")
      (node (ref "J1") (pin "11") (pinfunction "11_11") (pintype "passive"))
    )
    (net (code "77") (name "unconnected-(J1-Pad12)") (class "Default")
      (node (ref "J1") (pin "12") (pinfunction "12_12") (pintype "passive"))
    )
    (net (code "78") (name "unconnected-(J1-Pad13)") (class "Default")
      (node (ref "J1") (pin "13") (pinfunction "13_13") (pintype "passive"))
    )
    (net (code "79") (name "unconnected-(J1-Pad14)") (class "Default")
      (node (ref "J1") (pin "14") (pinfunction "14_14") (pintype "passive"))
    )
    (net (code "80") (name "unconnected-(J1-Pad15)") (class "Default")
      (node (ref "J1") (pin "15") (pinfunction "15_15") (pintype "passive"))
    )
    (net (code "81") (name "unconnected-(J1-Pad16)") (class "Default")
      (node (ref "J1") (pin "16") (pinfunction "16_16") (pintype "passive"))
    )
    (net (code "82") (name "unconnected-(J1-Pad17)") (class "Default")
      (node (ref "J1") (pin "17") (pinfunction "17_17") (pintype "passive"))
    )
    (net (code "83") (name "unconnected-(J1-Pad18)") (class "Default")
      (node (ref "J1") (pin "18") (pinfunction "18_18") (pintype "passive"))
    )
    (net (code "84") (name "unconnected-(J1-Pad19)") (class "Default")
      (node (ref "J1") (pin "19") (pinfunction "19_19") (pintype "passive"))
    )
    (net (code "85") (name "unconnected-(J1-Pad20)") (class "Default")
      (node (ref "J1") (pin "20") (pinfunction "20_20") (pintype "passive"))
    )
    (net (code "86") (name "unconnected-(J3-Pad6)") (class "Default")
      (node (ref "J3") (pin "6") (pinfunction "6_6") (pintype "bidirectional"))
    )
    (net (code "87") (name "unconnected-(J3-Pad7)") (class "Default")
      (node (ref "J3") (pin "7") (pinfunction "7_7") (pintype "bidirectional"))
    )
    (net (code "88") (name "unconnected-(J3-Pad8)") (class "Default")
      (node (ref "J3") (pin "8") (pinfunction "8_8") (pintype "bidirectional"))
    )
    (net (code "89") (name "unconnected-(U1A-IO,_(DATA0)-Pad13)") (class "Default")
      (node (ref "U1") (pin "13") (pinfunction "IO,_(DATA0)_13") (pintype "bidirectional"))
    )
    (net (code "90") (name "unconnected-(U1A-IO,_(DATA1,_ASDO)-Pad6)") (class "Default")
      (node (ref "U1") (pin "6") (pinfunction "IO,_(DATA1,_ASDO)_6") (pintype "bidirectional"))
    )
    (net (code "91") (name "unconnected-(U1A-IO,_(DQS0L{slash}CQ1L,DPCLK0)-Pad10)") (class "Default")
      (node (ref "U1") (pin "10") (pinfunction "IO,_(DQS0L/CQ1L,DPCLK0)_10") (pintype "bidirectional"))
    )
    (net (code "92") (name "unconnected-(U1A-IO,_VREFB1N0-Pad7)") (class "Default")
      (node (ref "U1") (pin "7") (pinfunction "IO,_VREFB1N0_7") (pintype "bidirectional"))
    )
    (net (code "93") (name "unconnected-(U1A-IO,_VREFB1N1-Pad11)") (class "Default")
      (node (ref "U1") (pin "11") (pinfunction "IO,_VREFB1N1_11") (pintype "bidirectional"))
    )
    (net (code "94") (name "unconnected-(U1A-IO-Pad4)") (class "Default")
      (node (ref "U1") (pin "4") (pinfunction "IO_4") (pintype "bidirectional"))
    )
    (net (code "95") (name "unconnected-(U1B-IO,_(DQS1L{slash}CQ1L#,DPCLK1)-Pad30)") (class "Default")
      (node (ref "U1") (pin "30") (pinfunction "IO,_(DQS1L/CQ1L#,DPCLK1)_30") (pintype "bidirectional"))
    )
    (net (code "96") (name "unconnected-(U1B-IO,_RDN1-Pad33)") (class "Default")
      (node (ref "U1") (pin "33") (pinfunction "IO,_RDN1_33") (pintype "bidirectional"))
    )
    (net (code "97") (name "unconnected-(U1B-IO,_RUP1-Pad32)") (class "Default")
      (node (ref "U1") (pin "32") (pinfunction "IO,_RUP1_32") (pintype "bidirectional"))
    )
    (net (code "98") (name "unconnected-(U1B-IO,_VREFB2N0-Pad28)") (class "Default")
      (node (ref "U1") (pin "28") (pinfunction "IO,_VREFB2N0_28") (pintype "bidirectional"))
    )
    (net (code "99") (name "unconnected-(U1B-IO,_VREFB2N1-Pad31)") (class "Default")
      (node (ref "U1") (pin "31") (pinfunction "IO,_VREFB2N1_31") (pintype "bidirectional"))
    )
    (net (code "100") (name "unconnected-(U1C-IO,_PLL1_CLKOUTn-Pad44)") (class "Default")
      (node (ref "U1") (pin "44") (pinfunction "IO,_PLL1_CLKOUTn_44") (pintype "bidirectional"))
    )
    (net (code "101") (name "unconnected-(U1C-IO,_PLL1_CLKOUTp-Pad43)") (class "Default")
      (node (ref "U1") (pin "43") (pinfunction "IO,_PLL1_CLKOUTp_43") (pintype "bidirectional"))
    )
    (net (code "102") (name "unconnected-(U1D-IO,_(DQS0B{slash}CQ1B,CDPCLK3)-Pad68)") (class "Default")
      (node (ref "U1") (pin "68") (pinfunction "IO,_(DQS0B/CQ1B,CDPCLK3)_68") (pintype "bidirectional"))
    )
    (net (code "103") (name "unconnected-(U1D-IO,_PLL4_CLKOUTn-Pad72)") (class "Default")
      (node (ref "U1") (pin "72") (pinfunction "IO,_PLL4_CLKOUTn_72") (pintype "bidirectional"))
    )
    (net (code "104") (name "unconnected-(U1D-IO,_PLL4_CLKOUTp-Pad71)") (class "Default")
      (node (ref "U1") (pin "71") (pinfunction "IO,_PLL4_CLKOUTp_71") (pintype "bidirectional"))
    )
    (net (code "105") (name "unconnected-(U1D-IO,_RDN2,_(DQ1B)-Pad67)") (class "Default")
      (node (ref "U1") (pin "67") (pinfunction "IO,_RDN2,_(DQ1B)_67") (pintype "bidirectional"))
    )
    (net (code "106") (name "unconnected-(U1D-IO,_RUP2,_(DQ1B)-Pad66)") (class "Default")
      (node (ref "U1") (pin "66") (pinfunction "IO,_RUP2,_(DQ1B)_66") (pintype "bidirectional"))
    )
    (net (code "107") (name "unconnected-(U1D-IO,_VREFB4N0-Pad69)") (class "Default")
      (node (ref "U1") (pin "69") (pinfunction "IO,_VREFB4N0_69") (pintype "bidirectional"))
    )
    (net (code "108") (name "unconnected-(U1E-IO,_(DQS1R{slash}CQ1R#,DPCLK6)-Pad85)") (class "Default")
      (node (ref "U1") (pin "85") (pinfunction "IO,_(DQS1R/CQ1R#,DPCLK6)_85") (pintype "bidirectional"))
    )
    (net (code "109") (name "unconnected-(U1E-IO,_DIFFIO_R21n,_(DEV_OE)-Pad86)") (class "Default")
      (node (ref "U1") (pin "86") (pinfunction "IO,_DIFFIO_R21n,_(DEV_OE)_86") (pintype "bidirectional"))
    )
    (net (code "110") (name "unconnected-(U1E-IO,_DIFFIO_R21p,_(DEV_CLRn)-Pad87)") (class "Default")
      (node (ref "U1") (pin "87") (pinfunction "IO,_DIFFIO_R21p,_(DEV_CLRn)_87") (pintype "bidirectional"))
    )
    (net (code "111") (name "unconnected-(U1E-IO,_RDN3-Pad77)") (class "Default")
      (node (ref "U1") (pin "77") (pinfunction "IO,_RDN3_77") (pintype "bidirectional"))
    )
    (net (code "112") (name "unconnected-(U1E-IO,_RUP3-Pad76)") (class "Default")
      (node (ref "U1") (pin "76") (pinfunction "IO,_RUP3_76") (pintype "bidirectional"))
    )
    (net (code "113") (name "unconnected-(U1E-IO,_VREFB5N0-Pad83)") (class "Default")
      (node (ref "U1") (pin "83") (pinfunction "IO,_VREFB5N0_83") (pintype "bidirectional"))
    )
    (net (code "114") (name "unconnected-(U1E-IO,_VREFB5N1-Pad80)") (class "Default")
      (node (ref "U1") (pin "80") (pinfunction "IO,_VREFB5N1_80") (pintype "bidirectional"))
    )
    (net (code "115") (name "unconnected-(U1E-IO-Pad79)") (class "Default")
      (node (ref "U1") (pin "79") (pinfunction "IO_79") (pintype "bidirectional"))
    )
    (net (code "116") (name "unconnected-(U1F-IO,_(DQS0R{slash}CQ1R,DPCLK7)-Pad104)") (class "Default")
      (node (ref "U1") (pin "104") (pinfunction "IO,_(DQS0R/CQ1R,DPCLK7)_104") (pintype "bidirectional"))
    )
    (net (code "117") (name "unconnected-(U1F-IO,_(PADD20)-Pad106)") (class "Default")
      (node (ref "U1") (pin "106") (pinfunction "IO,_(PADD20)_106") (pintype "bidirectional"))
    )
    (net (code "118") (name "unconnected-(U1F-IO,_DIFFIO_R16n,_(nCEO)-Pad101)") (class "Default")
      (node (ref "U1") (pin "101") (pinfunction "IO,_DIFFIO_R16n,_(nCEO)_101") (pintype "bidirectional"))
    )
    (net (code "119") (name "unconnected-(U1F-IO,_DIFFIO_R16p,_(CLKUSR)-Pad103)") (class "Default")
      (node (ref "U1") (pin "103") (pinfunction "IO,_DIFFIO_R16p,_(CLKUSR)_103") (pintype "bidirectional"))
    )
    (net (code "120") (name "unconnected-(U1F-IO,_DIFFIO_R17n,_(INIT_DONE)-Pad98)") (class "Default")
      (node (ref "U1") (pin "98") (pinfunction "IO,_DIFFIO_R17n,_(INIT_DONE)_98") (pintype "bidirectional"))
    )
    (net (code "121") (name "unconnected-(U1F-IO,_DIFFIO_R17p,_(CRC_ERROR)-Pad99)") (class "Default")
      (node (ref "U1") (pin "99") (pinfunction "IO,_DIFFIO_R17p,_(CRC_ERROR)_99") (pintype "bidirectional"))
    )
    (net (code "122") (name "unconnected-(U1F-IO,_VREFB6N0-Pad105)") (class "Default")
      (node (ref "U1") (pin "105") (pinfunction "IO,_VREFB6N0_105") (pintype "bidirectional"))
    )
    (net (code "123") (name "unconnected-(U1F-IO,_VREFB6N1-Pad100)") (class "Default")
      (node (ref "U1") (pin "100") (pinfunction "IO,_VREFB6N1_100") (pintype "bidirectional"))
    )
    (net (code "124") (name "unconnected-(U1G-IO,_(PADD3),_(DQ1T)-Pad120)") (class "Default")
      (node (ref "U1") (pin "120") (pinfunction "IO,_(PADD3),_(DQ1T)_120") (pintype "bidirectional"))
    )
    (net (code "125") (name "unconnected-(U1G-IO,_(PADD4)-Pad121)") (class "Default")
      (node (ref "U1") (pin "121") (pinfunction "IO,_(PADD4)_121") (pintype "bidirectional"))
    )
    (net (code "126") (name "unconnected-(U1G-IO,_(PADD12)-Pad125)") (class "Default")
      (node (ref "U1") (pin "125") (pinfunction "IO,_(PADD12)_125") (pintype "bidirectional"))
    )
    (net (code "127") (name "unconnected-(U1G-IO,_PLL2_CLKOUTn-Pad112)") (class "Default")
      (node (ref "U1") (pin "112") (pinfunction "IO,_PLL2_CLKOUTn_112") (pintype "bidirectional"))
    )
    (net (code "128") (name "unconnected-(U1G-IO,_PLL2_CLKOUTp-Pad113)") (class "Default")
      (node (ref "U1") (pin "113") (pinfunction "IO,_PLL2_CLKOUTp_113") (pintype "bidirectional"))
    )
    (net (code "129") (name "unconnected-(U1G-IO,_RDN4,_(DQ1T)-Pad115)") (class "Default")
      (node (ref "U1") (pin "115") (pinfunction "IO,_RDN4,_(DQ1T)_115") (pintype "bidirectional"))
    )
    (net (code "130") (name "unconnected-(U1G-IO,_RUP4,_(DQ1T)-Pad114)") (class "Default")
      (node (ref "U1") (pin "114") (pinfunction "IO,_RUP4,_(DQ1T)_114") (pintype "bidirectional"))
    )
    (net (code "131") (name "unconnected-(U1G-IO,_VREFB7N1-Pad119)") (class "Default")
      (node (ref "U1") (pin "119") (pinfunction "IO,_VREFB7N1_119") (pintype "bidirectional"))
    )
    (net (code "132") (name "unconnected-(U1H-IO,_(DATA5),_(DQ1T)-Pad137)") (class "Default")
      (node (ref "U1") (pin "137") (pinfunction "IO,_(DATA5),_(DQ1T)_137") (pintype "bidirectional"))
    )
    (net (code "133") (name "unconnected-(U1H-IO,_(DATA12),_(DQS1T{slash}CQ1T#,CDPCLK7)-Pad142)") (class "Default")
      (node (ref "U1") (pin "142") (pinfunction "IO,_(DATA12),_(DQS1T/CQ1T#,CDPCLK7)_142") (pintype "bidirectional"))
    )
    (net (code "134") (name "unconnected-(U1H-IO,_DIFFIO_T11p,_(DATA4),_(DQ1T)-Pad135)") (class "Default")
      (node (ref "U1") (pin "135") (pinfunction "IO,_DIFFIO_T11p,_(DATA4),_(DQ1T)_135") (pintype "bidirectional"))
    )
    (net (code "135") (name "unconnected-(U1H-IO,_VREFB8N0-Pad136)") (class "Default")
      (node (ref "U1") (pin "136") (pinfunction "IO,_VREFB8N0_136") (pintype "bidirectional"))
    )
    (net (code "136") (name "unconnected-(U1H-IO,_VREFB8N1-Pad141)") (class "Default")
      (node (ref "U1") (pin "141") (pinfunction "IO,_VREFB8N1_141") (pintype "bidirectional"))
    )
    (net (code "137") (name "unconnected-(U1M-GNDA1-Pad36)") (class "Default")
      (node (ref "U1") (pin "36") (pinfunction "GNDA1_36") (pintype "power_in"))
    )
    (net (code "138") (name "unconnected-(U4-A1A-Pad6)") (class "Default")
      (node (ref "U4") (pin "6") (pinfunction "A1A_6") (pintype "input"))
    )
    (net (code "139") (name "unconnected-(U4-A2A-Pad7)") (class "Default")
      (node (ref "U4") (pin "7") (pinfunction "A2A_7") (pintype "input"))
    )
    (net (code "140") (name "unconnected-(U4-B1A-Pad11)") (class "Default")
      (node (ref "U4") (pin "11") (pinfunction "B1A_11") (pintype "input"))
    )
    (net (code "141") (name "unconnected-(U4-B2A-Pad12)") (class "Default")
      (node (ref "U4") (pin "12") (pinfunction "B2A_12") (pintype "passive"))
    )
    (net (code "142") (name "unconnected-(U4-C3_N-Pad54)") (class "Default")
      (node (ref "U4") (pin "54") (pinfunction "C3_N_54") (pintype "passive"))
    )
    (net (code "143") (name "unconnected-(U4-C3_P-Pad53)") (class "Default")
      (node (ref "U4") (pin "53") (pinfunction "C3_P_53") (pintype "passive"))
    )
    (net (code "144") (name "unconnected-(U4-C4_N-Pad56)") (class "Default")
      (node (ref "U4") (pin "56") (pinfunction "C4_N_56") (pintype "passive"))
    )
    (net (code "145") (name "unconnected-(U4-C4_P-Pad55)") (class "Default")
      (node (ref "U4") (pin "55") (pinfunction "C4_P_55") (pintype "passive"))
    )
    (net (code "146") (name "unconnected-(U4-D3_N-Pad62)") (class "Default")
      (node (ref "U4") (pin "62") (pinfunction "D3_N_62") (pintype "passive"))
    )
    (net (code "147") (name "unconnected-(U4-D3_P-Pad61)") (class "Default")
      (node (ref "U4") (pin "61") (pinfunction "D3_P_61") (pintype "passive"))
    )
    (net (code "148") (name "unconnected-(U4-D4_N-Pad64)") (class "Default")
      (node (ref "U4") (pin "64") (pinfunction "D4_N_64") (pintype "passive"))
    )
    (net (code "149") (name "unconnected-(U4-D4_P-Pad63)") (class "Default")
      (node (ref "U4") (pin "63") (pinfunction "D4_P_63") (pintype "passive"))
    )
  )
)
